# Sheet1.net
KiCad netlist of a schematic drawn in Altium Designer
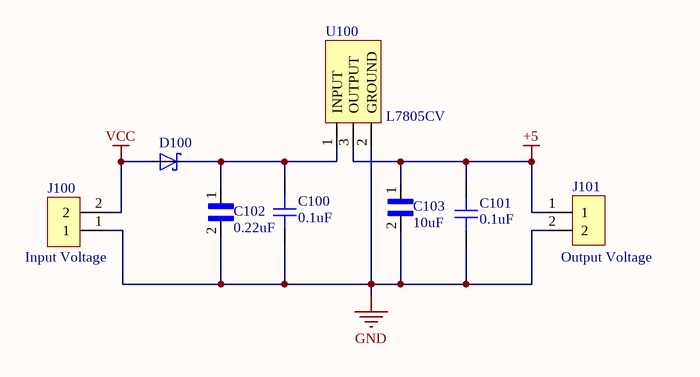
[diagram p0: Sheet1.SchDoc]

(export (version "E")
  (design (tool "Eeschema 10.0.6"))
  (components
    (comp (ref "C100")
      (value "0.1uF")
      (footprint "CAP_0603")
      (description "Capacitor SMD 0603 25V")
      (libsource (lib "Schematic-Lib-Zhrzkn") (part "CAP_0603_25V"))
    )
    (comp (ref "C101")
      (value "0.1uF")
      (footprint "CAP_0603")
      (description "Capacitor SMD 0603 25V")
      (libsource (lib "Schematic-Lib-Zhrzkn") (part "CAP_0603_25V"))
    )
    (comp (ref "C102")
      (value "0.22uF")
      (footprint "CAP-1210-X7R-10uF")
      (description "CAP CER 10UF 25V X7R 1210 / Cap Ceramic 10uF 25V X7R 10% Pad SMD 1210 125°C T/R")
      (fields
        (field (name "MANUFACTURER") "Samsung")
        (field (name "MANUFACTURER PART NUMBER") "CL32B106KAJNNNE")
      )
      (libsource (lib "Schematic-Lib-Zhrzkn") (part "CAP-1210-X7R-10uF"))
    )
    (comp (ref "C103")
      (value "10uF")
      (footprint "CAP-1210-X7R-10uF")
      (description "CAP CER 10UF 25V X7R 1210 / Cap Ceramic 10uF 25V X7R 10% Pad SMD 1210 125°C T/R")
      (fields
        (field (name "MANUFACTURER") "Samsung")
        (field (name "MANUFACTURER PART NUMBER") "CL32B106KAJNNNE")
      )
      (libsource (lib "") (part "CAP-1210-X7R-10uF_1"))
    )
    (comp (ref "D100")
      (value "1PS79SB70")
      (footprint "DIODE_SCHOTTKY")
      (libsource (lib "Schematic-Lib-Zhrzkn") (part "Schottky_Diode"))
    )
    (comp (ref "J100")
      (value "Input Voltage")
      (footprint "HEADER_2")
      (libsource (lib "") (part "Terminal_Block_2_1"))
    )
    (comp (ref "J101")
      (value "Output Voltage")
      (footprint "HEADER_2")
      (libsource (lib "Schematic-Lib-Zhrzkn") (part "Terminal_Block_2"))
    )
    (comp (ref "U100")
      (value "L7805CV")
      (footprint "L7805CV")
      (libsource (lib "Schematic-Lib-Zhrzkn") (part "L7805CV"))
    )
  )
  (nets
    (net (code "1") (name "+5") (class "Default")
      (node (ref "C101") (pin "2") (pinfunction "2_2") (pintype "passive"))
      (node (ref "C103") (pin "1") (pinfunction "1_1") (pintype "passive"))
      (node (ref "J101") (pin "1") (pinfunction "1_1") (pintype "passive"))
      (node (ref "U100") (pin "3") (pinfunction "OUTPUT_3") (pintype "passive"))
    )
    (net (code "2") (name "GND") (class "Default")
      (node (ref "C100") (pin "1") (pinfunction "1_1") (pintype "passive"))
      (node (ref "C101") (pin "1") (pinfunction "1_1") (pintype "passive"))
      (node (ref "C102") (pin "2") (pinfunction "2_2") (pintype "passive"))
      (node (ref "C103") (pin "2") (pinfunction "2_2") (pintype "passive"))
      (node (ref "J100") (pin "1") (pinfunction "1_1") (pintype "passive"))
      (node (ref "J101") (pin "2") (pinfunction "2_2") (pintype "passive"))
      (node (ref "U100") (pin "2") (pinfunction "GROUND_2") (pintype "passive"))
    )
    (net (code "3") (name "Net-(D100-K)") (class "Default")
      (node (ref "C100") (pin "2") (pinfunction "2_2") (pintype "passive"))
      (node (ref "C102") (pin "1") (pinfunction "1_1") (pintype "passive"))
      (node (ref "D100") (pin "1") (pinfunction "K_1") (pintype "passive"))
      (node (ref "U100") (pin "1") (pinfunction "INPUT_1") (pintype "passive"))
    )
    (net (code "4") (name "VCC") (class "Default")
      (node (ref "D100") (pin "2") (pinfunction "A_2") (pintype "passive"))
      (node (ref "J100") (pin "2") (pinfunction "2_2") (pintype "passive"))
    )
  )
)
